# atmega4089-breakout.net
KiCad netlist of a schematic drawn in EAGLE
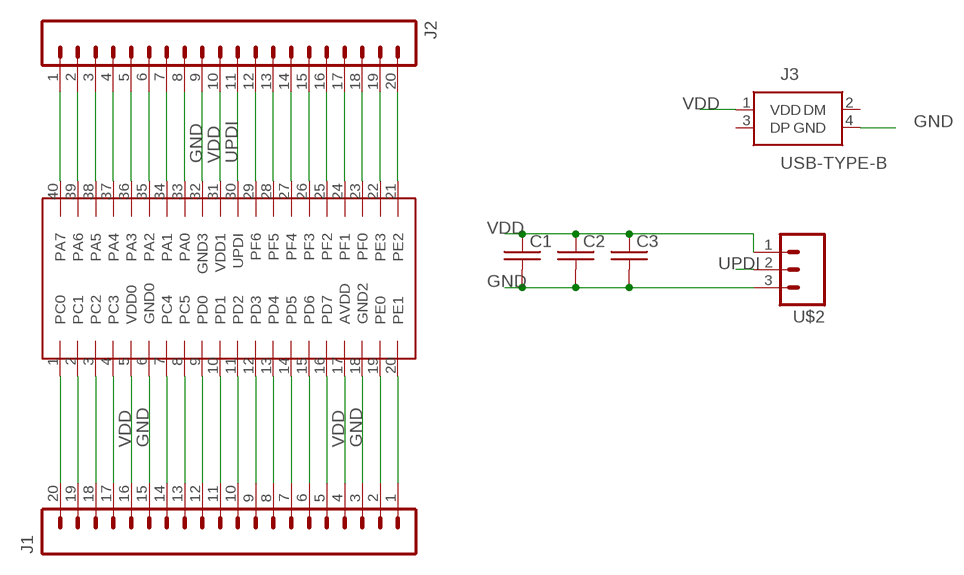
[diagram p0: schematic, sheet 1]

(export (version "E")
  (design (tool "Eeschema 10.0.6"))
  (components
    (comp (ref "C1")
      (value "C-USC0805")
      (footprint "eagle-import:C0805")
      (libsource (lib "eagle-import") (part "C-USC0805"))
    )
    (comp (ref "C2")
      (value "C-USC0805")
      (footprint "eagle-import:C0805")
      (libsource (lib "eagle-import") (part "C-USC0805"))
    )
    (comp (ref "C3")
      (value "C-USC0805")
      (footprint "eagle-import:C0805")
      (libsource (lib "eagle-import") (part "C-USC0805"))
    )
    (comp (ref "J1")
      (value "M20")
      (footprint "eagle-import:1X20")
      (libsource (lib "eagle-import") (part "M20"))
    )
    (comp (ref "J2")
      (value "M20")
      (footprint "eagle-import:1X20")
      (libsource (lib "eagle-import") (part "M20"))
    )
    (comp (ref "J3")
      (value "USB-TYPE-B")
      (footprint "eagle-import:61400413321")
      (fields
        (field (name "MANUFACTURER_PART_NUMBER") "61400413321")
        (field (name "MOUSER_PART_NUMBER") "710-61400413321")
      )
      (libsource (lib "eagle-import") (part "USB-TYPE-B"))
    )
    (comp (ref "U$1")
      (value "ATMEGA4809-PFATMEL4809-PF")
      (footprint "eagle-import:DIP1587W58P254L5175H635Q40B")
      (libsource (lib "eagle-import") (part "ATMEGA4809-PFATMEL4809-PF"))
    )
    (comp (ref "U$2")
      (value "M03")
      (footprint "eagle-import:1X03_UDPI")
      (libsource (lib "eagle-import") (part "M03"))
    )
  )
  (nets
    (net (code "1") (name "/GND") (class "Default")
      (node (ref "C1") (pin "2") (pinfunction "2_2") (pintype "passive"))
      (node (ref "C2") (pin "2") (pinfunction "2_2") (pintype "passive"))
      (node (ref "C3") (pin "2") (pinfunction "2_2") (pintype "passive"))
      (node (ref "J1") (pin "15") (pinfunction "15_15") (pintype "passive"))
      (node (ref "J1") (pin "3") (pinfunction "3_3") (pintype "passive"))
      (node (ref "J2") (pin "9") (pinfunction "9_9") (pintype "passive"))
      (node (ref "J3") (pin "4") (pinfunction "GND_4") (pintype "bidirectional"))
      (node (ref "U$1") (pin "18") (pinfunction "GND2_18") (pintype "bidirectional"))
      (node (ref "U$1") (pin "32") (pinfunction "GND3_32") (pintype "bidirectional"))
      (node (ref "U$1") (pin "6") (pinfunction "GND0_6") (pintype "bidirectional"))
      (node (ref "U$2") (pin "3") (pinfunction "3_3") (pintype "passive"))
    )
    (net (code "2") (name "/UPDI") (class "Default")
      (node (ref "J2") (pin "11") (pinfunction "11_11") (pintype "passive"))
      (node (ref "U$1") (pin "30") (pinfunction "UPDI_30") (pintype "bidirectional"))
      (node (ref "U$2") (pin "2") (pinfunction "2_2") (pintype "passive"))
    )
    (net (code "3") (name "/VDD") (class "Default")
      (node (ref "C1") (pin "1") (pinfunction "1_1") (pintype "passive"))
      (node (ref "C2") (pin "1") (pinfunction "1_1") (pintype "passive"))
      (node (ref "C3") (pin "1") (pinfunction "1_1") (pintype "passive"))
      (node (ref "J1") (pin "16") (pinfunction "16_16") (pintype "passive"))
      (node (ref "J1") (pin "4") (pinfunction "4_4") (pintype "passive"))
      (node (ref "J2") (pin "10") (pinfunction "10_10") (pintype "passive"))
      (node (ref "J3") (pin "1") (pinfunction "VDD_1") (pintype "bidirectional"))
      (node (ref "U$1") (pin "17") (pinfunction "AVDD_17") (pintype "power_in"))
      (node (ref "U$1") (pin "31") (pinfunction "VDD1_31") (pintype "power_in"))
      (node (ref "U$1") (pin "5") (pinfunction "VDD0_5") (pintype "power_in"))
      (node (ref "U$2") (pin "1") (pinfunction "1_1") (pintype "passive"))
    )
    (net (code "4") (name "Net-(U$1-PA0)") (class "Default")
      (node (ref "J2") (pin "8") (pinfunction "8_8") (pintype "passive"))
      (node (ref "U$1") (pin "33") (pinfunction "PA0_33") (pintype "bidirectional"))
    )
    (net (code "5") (name "Net-(U$1-PA1)") (class "Default")
      (node (ref "J2") (pin "7") (pinfunction "7_7") (pintype "passive"))
      (node (ref "U$1") (pin "34") (pinfunction "PA1_34") (pintype "bidirectional"))
    )
    (net (code "6") (name "Net-(U$1-PA2)") (class "Default")
      (node (ref "J2") (pin "6") (pinfunction "6_6") (pintype "passive"))
      (node (ref "U$1") (pin "35") (pinfunction "PA2_35") (pintype "bidirectional"))
    )
    (net (code "7") (name "Net-(U$1-PA3)") (class "Default")
      (node (ref "J2") (pin "5") (pinfunction "5_5") (pintype "passive"))
      (node (ref "U$1") (pin "36") (pinfunction "PA3_36") (pintype "bidirectional"))
    )
    (net (code "8") (name "Net-(U$1-PA4)") (class "Default")
      (node (ref "J2") (pin "4") (pinfunction "4_4") (pintype "passive"))
      (node (ref "U$1") (pin "37") (pinfunction "PA4_37") (pintype "bidirectional"))
    )
    (net (code "9") (name "Net-(U$1-PA5)") (class "Default")
      (node (ref "J2") (pin "3") (pinfunction "3_3") (pintype "passive"))
      (node (ref "U$1") (pin "38") (pinfunction "PA5_38") (pintype "bidirectional"))
    )
    (net (code "10") (name "Net-(U$1-PA6)") (class "Default")
      (node (ref "J2") (pin "2") (pinfunction "2_2") (pintype "passive"))
      (node (ref "U$1") (pin "39") (pinfunction "PA6_39") (pintype "bidirectional"))
    )
    (net (code "11") (name "Net-(U$1-PA7)") (class "Default")
      (node (ref "J2") (pin "1") (pinfunction "1_1") (pintype "passive"))
      (node (ref "U$1") (pin "40") (pinfunction "PA7_40") (pintype "bidirectional"))
    )
    (net (code "12") (name "Net-(U$1-PC0)") (class "Default")
      (node (ref "J1") (pin "20") (pinfunction "20_20") (pintype "passive"))
      (node (ref "U$1") (pin "1") (pinfunction "PC0_1") (pintype "bidirectional"))
    )
    (net (code "13") (name "Net-(U$1-PC1)") (class "Default")
      (node (ref "J1") (pin "19") (pinfunction "19_19") (pintype "passive"))
      (node (ref "U$1") (pin "2") (pinfunction "PC1_2") (pintype "bidirectional"))
    )
    (net (code "14") (name "Net-(U$1-PC2)") (class "Default")
      (node (ref "J1") (pin "18") (pinfunction "18_18") (pintype "passive"))
      (node (ref "U$1") (pin "3") (pinfunction "PC2_3") (pintype "bidirectional"))
    )
    (net (code "15") (name "Net-(U$1-PC3)") (class "Default")
      (node (ref "J1") (pin "17") (pinfunction "17_17") (pintype "passive"))
      (node (ref "U$1") (pin "4") (pinfunction "PC3_4") (pintype "bidirectional"))
    )
    (net (code "16") (name "Net-(U$1-PC4)") (class "Default")
      (node (ref "J1") (pin "14") (pinfunction "14_14") (pintype "passive"))
      (node (ref "U$1") (pin "7") (pinfunction "PC4_7") (pintype "bidirectional"))
    )
    (net (code "17") (name "Net-(U$1-PC5)") (class "Default")
      (node (ref "J1") (pin "13") (pinfunction "13_13") (pintype "passive"))
      (node (ref "U$1") (pin "8") (pinfunction "PC5_8") (pintype "bidirectional"))
    )
    (net (code "18") (name "Net-(U$1-PD0)") (class "Default")
      (node (ref "J1") (pin "12") (pinfunction "12_12") (pintype "passive"))
      (node (ref "U$1") (pin "9") (pinfunction "PD0_9") (pintype "bidirectional"))
    )
    (net (code "19") (name "Net-(U$1-PD1)") (class "Default")
      (node (ref "J1") (pin "11") (pinfunction "11_11") (pintype "passive"))
      (node (ref "U$1") (pin "10") (pinfunction "PD1_10") (pintype "bidirectional"))
    )
    (net (code "20") (name "Net-(U$1-PD2)") (class "Default")
      (node (ref "J1") (pin "10") (pinfunction "10_10") (pintype "passive"))
      (node (ref "U$1") (pin "11") (pinfunction "PD2_11") (pintype "bidirectional"))
    )
    (net (code "21") (name "Net-(U$1-PD3)") (class "Default")
      (node (ref "J1") (pin "9") (pinfunction "9_9") (pintype "passive"))
      (node (ref "U$1") (pin "12") (pinfunction "PD3_12") (pintype "bidirectional"))
    )
    (net (code "22") (name "Net-(U$1-PD4)") (class "Default")
      (node (ref "J1") (pin "8") (pinfunction "8_8") (pintype "passive"))
      (node (ref "U$1") (pin "13") (pinfunction "PD4_13") (pintype "bidirectional"))
    )
    (net (code "23") (name "Net-(U$1-PD5)") (class "Default")
      (node (ref "J1") (pin "7") (pinfunction "7_7") (pintype "passive"))
      (node (ref "U$1") (pin "14") (pinfunction "PD5_14") (pintype "bidirectional"))
    )
    (net (code "24") (name "Net-(U$1-PD6)") (class "Default")
      (node (ref "J1") (pin "6") (pinfunction "6_6") (pintype "passive"))
      (node (ref "U$1") (pin "15") (pinfunction "PD6_15") (pintype "bidirectional"))
    )
    (net (code "25") (name "Net-(U$1-PD7)") (class "Default")
      (node (ref "J1") (pin "5") (pinfunction "5_5") (pintype "passive"))
      (node (ref "U$1") (pin "16") (pinfunction "PD7_16") (pintype "bidirectional"))
    )
    (net (code "26") (name "Net-(U$1-PE0)") (class "Default")
      (node (ref "J1") (pin "2") (pinfunction "2_2") (pintype "passive"))
      (node (ref "U$1") (pin "19") (pinfunction "PE0_19") (pintype "bidirectional"))
    )
    (net (code "27") (name "Net-(U$1-PE1)") (class "Default")
      (node (ref "J1") (pin "1") (pinfunction "1_1") (pintype "passive"))
      (node (ref "U$1") (pin "20") (pinfunction "PE1_20") (pintype "bidirectional"))
    )
    (net (code "28") (name "Net-(U$1-PE2)") (class "Default")
      (node (ref "J2") (pin "20") (pinfunction "20_20") (pintype "passive"))
      (node (ref "U$1") (pin "21") (pinfunction "PE2_21") (pintype "bidirectional"))
    )
    (net (code "29") (name "Net-(U$1-PE3)") (class "Default")
      (node (ref "J2") (pin "19") (pinfunction "19_19") (pintype "passive"))
      (node (ref "U$1") (pin "22") (pinfunction "PE3_22") (pintype "bidirectional"))
    )
    (net (code "30") (name "Net-(U$1-PF0)") (class "Default")
      (node (ref "J2") (pin "18") (pinfunction "18_18") (pintype "passive"))
      (node (ref "U$1") (pin "23") (pinfunction "PF0_23") (pintype "bidirectional"))
    )
    (net (code "31") (name "Net-(U$1-PF1)") (class "Default")
      (node (ref "J2") (pin "17") (pinfunction "17_17") (pintype "passive"))
      (node (ref "U$1") (pin "24") (pinfunction "PF1_24") (pintype "bidirectional"))
    )
    (net (code "32") (name "Net-(U$1-PF2)") (class "Default")
      (node (ref "J2") (pin "16") (pinfunction "16_16") (pintype "passive"))
      (node (ref "U$1") (pin "25") (pinfunction "PF2_25") (pintype "bidirectional"))
    )
    (net (code "33") (name "Net-(U$1-PF3)") (class "Default")
      (node (ref "J2") (pin "15") (pinfunction "15_15") (pintype "passive"))
      (node (ref "U$1") (pin "26") (pinfunction "PF3_26") (pintype "bidirectional"))
    )
    (net (code "34") (name "Net-(U$1-PF4)") (class "Default")
      (node (ref "J2") (pin "14") (pinfunction "14_14") (pintype "passive"))
      (node (ref "U$1") (pin "27") (pinfunction "PF4_27") (pintype "bidirectional"))
    )
    (net (code "35") (name "Net-(U$1-PF5)") (class "Default")
      (node (ref "J2") (pin "13") (pinfunction "13_13") (pintype "passive"))
      (node (ref "U$1") (pin "28") (pinfunction "PF5_28") (pintype "bidirectional"))
    )
    (net (code "36") (name "Net-(U$1-PF6)") (class "Default")
      (node (ref "J2") (pin "12") (pinfunction "12_12") (pintype "passive"))
      (node (ref "U$1") (pin "29") (pinfunction "PF6_29") (pintype "bidirectional"))
    )
    (net (code "37") (name "unconnected-(J3-DM-Pad2)") (class "Default")
      (node (ref "J3") (pin "2") (pinfunction "DM_2") (pintype "bidirectional"))
    )
    (net (code "38") (name "unconnected-(J3-DP-Pad3)") (class "Default")
      (node (ref "J3") (pin "3") (pinfunction "DP_3") (pintype "bidirectional"))
    )
  )
)
